# Smoothie_Stamp_Carrier_A3.net
KiCad netlist of a schematic drawn in EAGLE
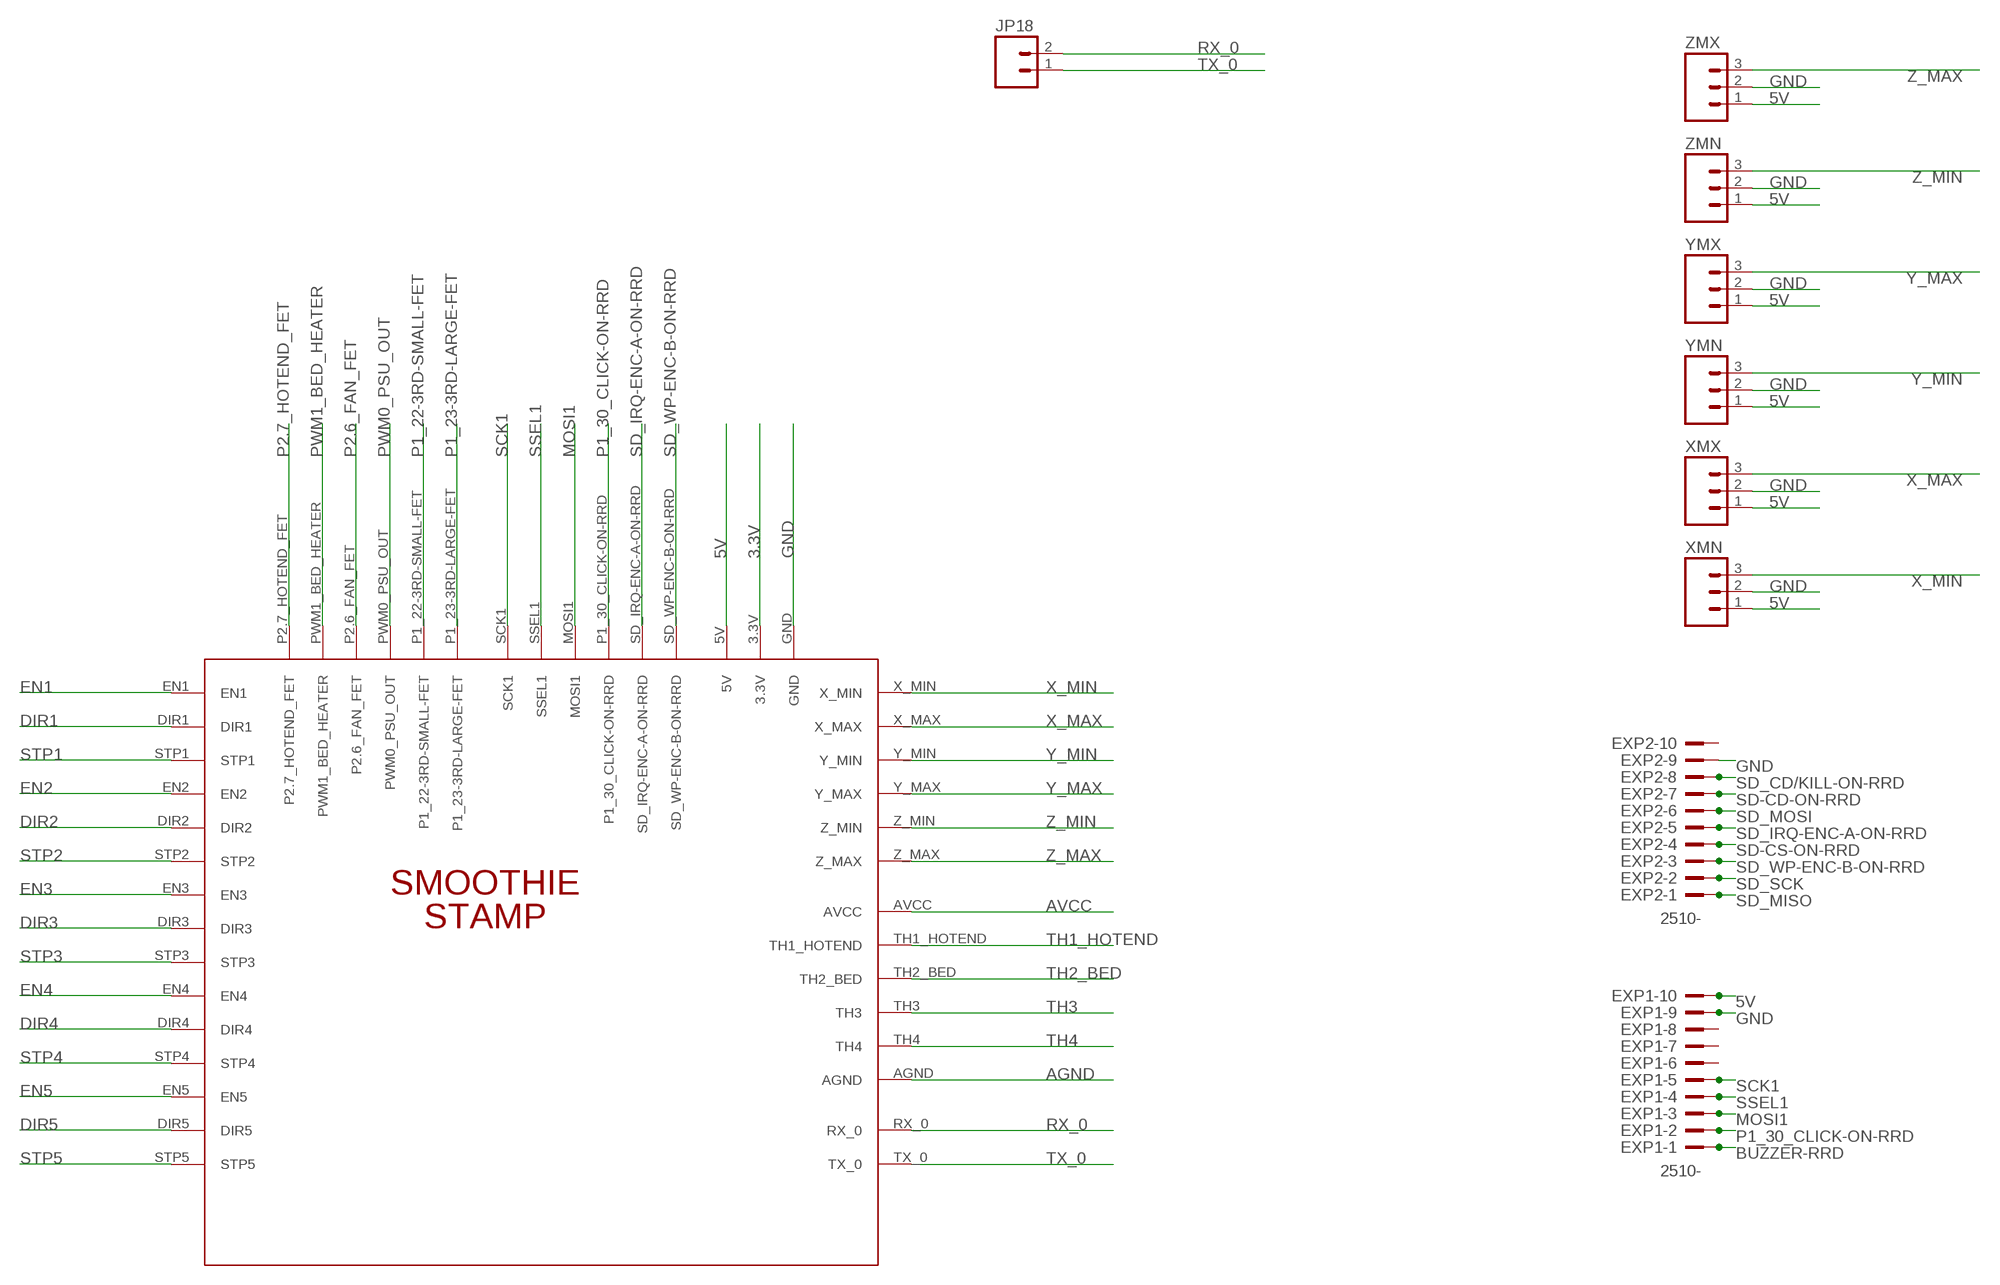
[diagram p0: schematic, sheet 1]
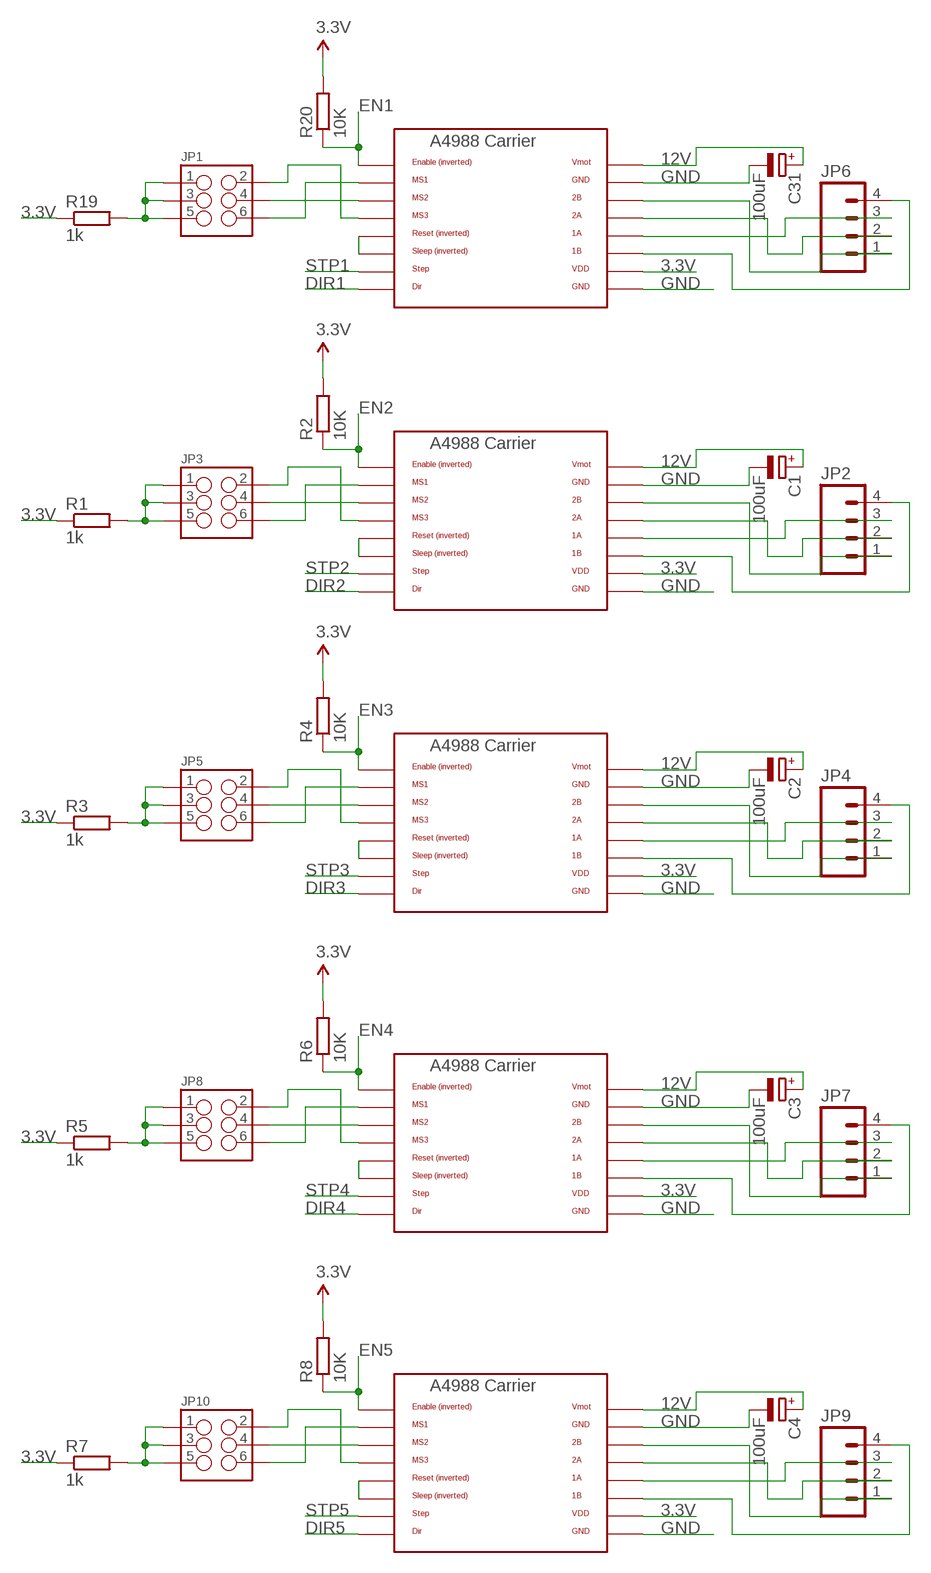
[diagram p1: schematic, sheet 2]
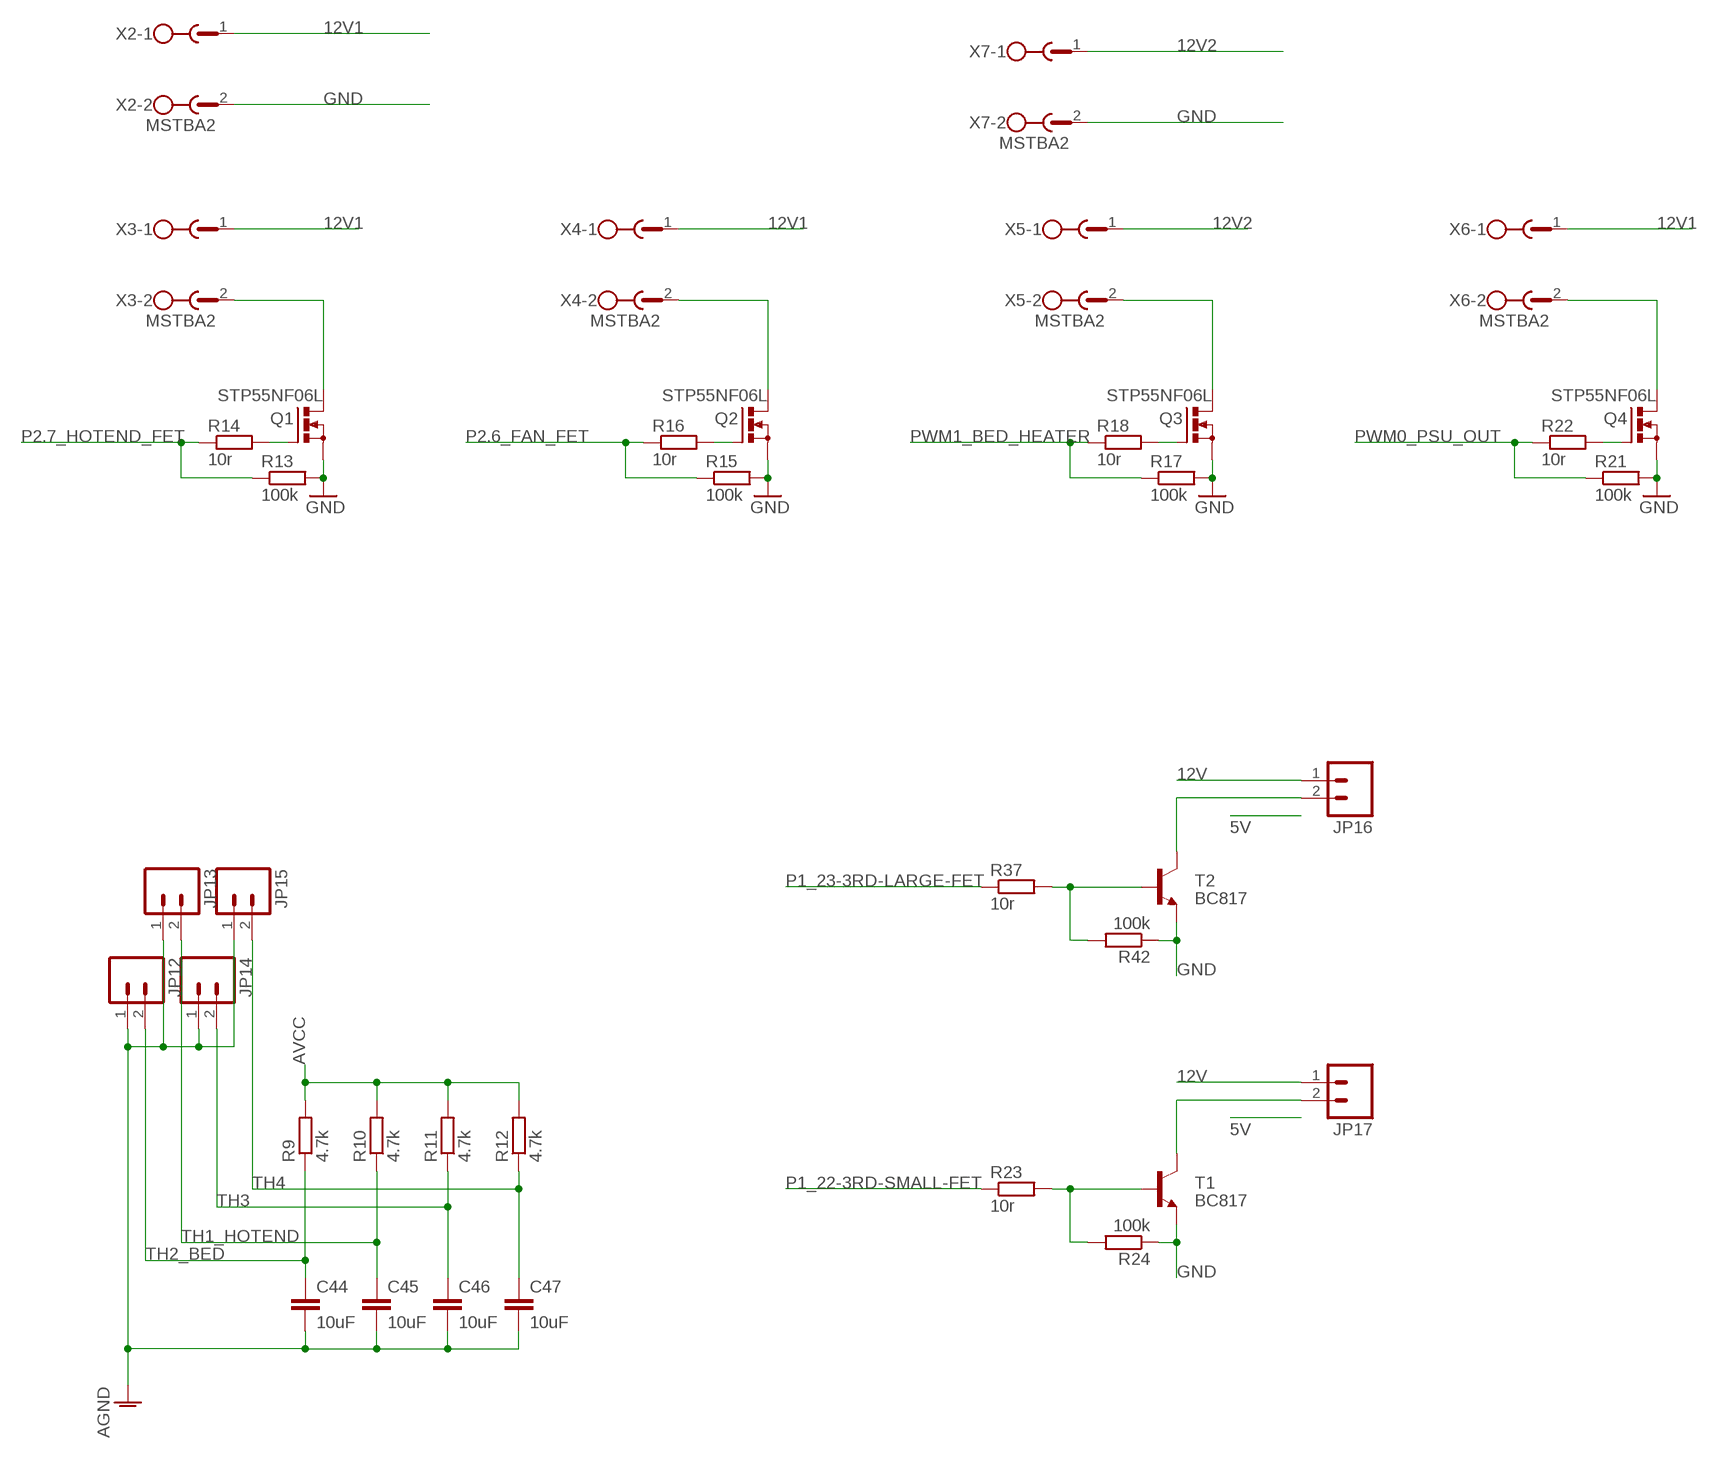
[diagram p2: schematic, sheet 3]
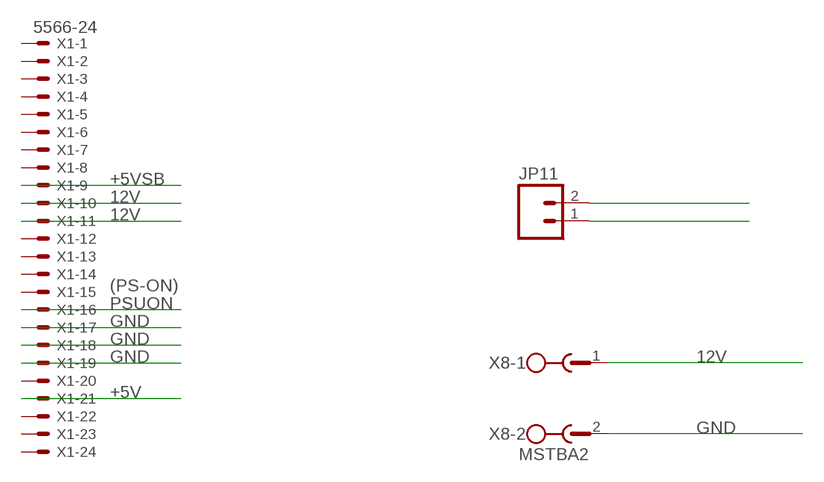
[diagram p3: schematic, sheet 4]

(export (version "E")
  (design (tool "Eeschema 10.0.6"))
  (components
    (comp (ref "EXP1")
      (value "2510-")
      (footprint "eagle-import:PAK100_2500-10")
      (fields (field (name "MF") "3M") (field (name "MPN") "2510-6002UB"))
      (libsource (lib "eagle-import") (part "2510-"))
    )
    (comp (ref "EXP2")
      (value "2510-")
      (footprint "eagle-import:PAK100_2500-10")
      (fields (field (name "MF") "3M") (field (name "MPN") "2510-6002UB"))
      (libsource (lib "eagle-import") (part "2510-"))
    )
    (comp (ref "JP18")
      (value "M02LOCK")
      (footprint "eagle-import:1X02_LOCK")
      (libsource (lib "eagle-import") (part "M02LOCK"))
    )
    (comp (ref "U$1")
      (value "SMOOTHIE-STAMPSMOOTHIE-STAMP-PTH")
      (footprint "eagle-import:SMOOTHIE-STAMP-PTH")
      (libsource (lib "eagle-import") (part "SMOOTHIE-STAMPSMOOTHIE-STAMP-PTH"))
    )
    (comp (ref "XMN")
      (value "M03LOCK")
      (footprint "eagle-import:1X03_LOCK")
      (libsource (lib "eagle-import") (part "M03LOCK"))
    )
    (comp (ref "XMX")
      (value "M03LOCK")
      (footprint "eagle-import:1X03_LOCK")
      (libsource (lib "eagle-import") (part "M03LOCK"))
    )
    (comp (ref "YMN")
      (value "M03LOCK")
      (footprint "eagle-import:1X03_LOCK")
      (libsource (lib "eagle-import") (part "M03LOCK"))
    )
    (comp (ref "YMX")
      (value "M03LOCK")
      (footprint "eagle-import:1X03_LOCK")
      (libsource (lib "eagle-import") (part "M03LOCK"))
    )
    (comp (ref "ZMN")
      (value "M03LOCK")
      (footprint "eagle-import:1X03_LOCK")
      (libsource (lib "eagle-import") (part "M03LOCK"))
    )
    (comp (ref "ZMX")
      (value "M03LOCK")
      (footprint "eagle-import:1X03_LOCK")
      (libsource (lib "eagle-import") (part "M03LOCK"))
    )
    (comp (ref "JP11")
      (value "M02LOCK")
      (footprint "eagle-import:1X02_LOCK")
      (libsource (lib "eagle-import") (part "M02LOCK"))
    )
    (comp (ref "X1")
      (value "5566-24")
      (footprint "eagle-import:5566-24")
      (libsource (lib "eagle-import") (part "5566-24"))
    )
    (comp (ref "X8")
      (value "MSTBA2")
      (footprint "eagle-import:MSTBA2")
      (fields (field (name "MF") "FARNELL") (field (name "MPN") "1757242"))
      (libsource (lib "eagle-import") (part "MSTBA2"))
    )
    (comp (ref "C1")
      (value "100uF")
      (footprint "eagle-import:E3,5-8")
      (libsource (lib "eagle-import") (part "CPOL-EUE3.5-8"))
    )
    (comp (ref "C2")
      (value "100uF")
      (footprint "eagle-import:E3,5-8")
      (libsource (lib "eagle-import") (part "CPOL-EUE3.5-8"))
    )
    (comp (ref "C3")
      (value "100uF")
      (footprint "eagle-import:E3,5-8")
      (libsource (lib "eagle-import") (part "CPOL-EUE3.5-8"))
    )
    (comp (ref "C4")
      (value "100uF")
      (footprint "eagle-import:E3,5-8")
      (libsource (lib "eagle-import") (part "CPOL-EUE3.5-8"))
    )
    (comp (ref "C31")
      (value "100uF")
      (footprint "eagle-import:E3,5-8")
      (libsource (lib "eagle-import") (part "CPOL-EUE3.5-8"))
    )
    (comp (ref "JP1")
      (value "M03X22X3_SILK_MALE_PTH")
      (footprint "eagle-import:2X3")
      (libsource (lib "eagle-import") (part "M03X22X3_SILK_MALE_PTH"))
    )
    (comp (ref "JP2")
      (value "M04POLAR_LOCK")
      (footprint "eagle-import:MOLEX-1X4_LOCK")
      (libsource (lib "eagle-import") (part "M04POLAR_LOCK"))
    )
    (comp (ref "JP3")
      (value "M03X22X3_SILK_MALE_PTH")
      (footprint "eagle-import:2X3")
      (libsource (lib "eagle-import") (part "M03X22X3_SILK_MALE_PTH"))
    )
    (comp (ref "JP4")
      (value "M04POLAR_LOCK")
      (footprint "eagle-import:MOLEX-1X4_LOCK")
      (libsource (lib "eagle-import") (part "M04POLAR_LOCK"))
    )
    (comp (ref "JP5")
      (value "M03X22X3_SILK_MALE_PTH")
      (footprint "eagle-import:2X3")
      (libsource (lib "eagle-import") (part "M03X22X3_SILK_MALE_PTH"))
    )
    (comp (ref "JP6")
      (value "M04POLAR_LOCK")
      (footprint "eagle-import:MOLEX-1X4_LOCK")
      (libsource (lib "eagle-import") (part "M04POLAR_LOCK"))
    )
    (comp (ref "JP7")
      (value "M04POLAR_LOCK")
      (footprint "eagle-import:MOLEX-1X4_LOCK")
      (libsource (lib "eagle-import") (part "M04POLAR_LOCK"))
    )
    (comp (ref "JP8")
      (value "M03X22X3_SILK_MALE_PTH")
      (footprint "eagle-import:2X3")
      (libsource (lib "eagle-import") (part "M03X22X3_SILK_MALE_PTH"))
    )
    (comp (ref "JP9")
      (value "M04POLAR_LOCK")
      (footprint "eagle-import:MOLEX-1X4_LOCK")
      (libsource (lib "eagle-import") (part "M04POLAR_LOCK"))
    )
    (comp (ref "JP10")
      (value "M03X22X3_SILK_MALE_PTH")
      (footprint "eagle-import:2X3")
      (libsource (lib "eagle-import") (part "M03X22X3_SILK_MALE_PTH"))
    )
    (comp (ref "R1")
      (value "1k")
      (footprint "eagle-import:0204V")
      (libsource (lib "eagle-import") (part "R-EU_0204/2V"))
    )
    (comp (ref "R2")
      (value "10K")
      (footprint "eagle-import:0204V")
      (libsource (lib "eagle-import") (part "R-EU_0204/2V"))
    )
    (comp (ref "R3")
      (value "1k")
      (footprint "eagle-import:0204V")
      (libsource (lib "eagle-import") (part "R-EU_0204/2V"))
    )
    (comp (ref "R4")
      (value "10K")
      (footprint "eagle-import:0204V")
      (libsource (lib "eagle-import") (part "R-EU_0204/2V"))
    )
    (comp (ref "R5")
      (value "1k")
      (footprint "eagle-import:0204V")
      (libsource (lib "eagle-import") (part "R-EU_0204/2V"))
    )
    (comp (ref "R6")
      (value "10K")
      (footprint "eagle-import:0204V")
      (libsource (lib "eagle-import") (part "R-EU_0204/2V"))
    )
    (comp (ref "R7")
      (value "1k")
      (footprint "eagle-import:0204V")
      (libsource (lib "eagle-import") (part "R-EU_0204/2V"))
    )
    (comp (ref "R8")
      (value "10K")
      (footprint "eagle-import:0204V")
      (libsource (lib "eagle-import") (part "R-EU_0204/2V"))
    )
    (comp (ref "R19")
      (value "1k")
      (footprint "eagle-import:0204V")
      (libsource (lib "eagle-import") (part "R-EU_0204/2V"))
    )
    (comp (ref "R20")
      (value "10K")
      (footprint "eagle-import:0204V")
      (libsource (lib "eagle-import") (part "R-EU_0204/2V"))
    )
    (comp (ref "U$2")
      (value "POLOLU_A4983CARRIER")
      (footprint "eagle-import:A4988BREAKOUT")
      (libsource (lib "eagle-import") (part "POLOLU_A4983CARRIER"))
    )
    (comp (ref "U$3")
      (value "POLOLU_A4983CARRIER")
      (footprint "eagle-import:A4988BREAKOUT")
      (libsource (lib "eagle-import") (part "POLOLU_A4983CARRIER"))
    )
    (comp (ref "U$4")
      (value "POLOLU_A4983CARRIER")
      (footprint "eagle-import:A4988BREAKOUT")
      (libsource (lib "eagle-import") (part "POLOLU_A4983CARRIER"))
    )
    (comp (ref "U$5")
      (value "POLOLU_A4983CARRIER")
      (footprint "eagle-import:A4988BREAKOUT")
      (libsource (lib "eagle-import") (part "POLOLU_A4983CARRIER"))
    )
    (comp (ref "U$6")
      (value "POLOLU_A4983CARRIER")
      (footprint "eagle-import:A4988BREAKOUT")
      (libsource (lib "eagle-import") (part "POLOLU_A4983CARRIER"))
    )
    (comp (ref "C44")
      (value "10uF")
      (footprint "eagle-import:C050-025X075")
      (libsource (lib "eagle-import") (part "C-EU050-025X075"))
    )
    (comp (ref "C45")
      (value "10uF")
      (footprint "eagle-import:C050-025X075")
      (libsource (lib "eagle-import") (part "C-EU050-025X075"))
    )
    (comp (ref "C46")
      (value "10uF")
      (footprint "eagle-import:C050-025X075")
      (libsource (lib "eagle-import") (part "C-EU050-025X075"))
    )
    (comp (ref "C47")
      (value "10uF")
      (footprint "eagle-import:C050-025X075")
      (libsource (lib "eagle-import") (part "C-EU050-025X075"))
    )
    (comp (ref "JP12")
      (value "M02PTH")
      (footprint "eagle-import:1X02")
      (libsource (lib "eagle-import") (part "M02PTH"))
    )
    (comp (ref "JP13")
      (value "M02PTH")
      (footprint "eagle-import:1X02")
      (libsource (lib "eagle-import") (part "M02PTH"))
    )
    (comp (ref "JP14")
      (value "M02PTH")
      (footprint "eagle-import:1X02")
      (libsource (lib "eagle-import") (part "M02PTH"))
    )
    (comp (ref "JP15")
      (value "M02PTH")
      (footprint "eagle-import:1X02")
      (libsource (lib "eagle-import") (part "M02PTH"))
    )
    (comp (ref "JP16")
      (value "M02LOCK")
      (footprint "eagle-import:1X02_LOCK")
      (libsource (lib "eagle-import") (part "M02LOCK"))
    )
    (comp (ref "JP17")
      (value "M02LOCK")
      (footprint "eagle-import:1X02_LOCK")
      (libsource (lib "eagle-import") (part "M02LOCK"))
    )
    (comp (ref "Q1")
      (value "STP55NF06L")
      (footprint "eagle-import:TO220BV")
      (libsource (lib "eagle-import") (part "IRF512"))
    )
    (comp (ref "Q2")
      (value "STP55NF06L")
      (footprint "eagle-import:TO220BV")
      (libsource (lib "eagle-import") (part "IRF512"))
    )
    (comp (ref "Q3")
      (value "STP55NF06L")
      (footprint "eagle-import:TO220BV")
      (libsource (lib "eagle-import") (part "IRF512"))
    )
    (comp (ref "Q4")
      (value "STP55NF06L")
      (footprint "eagle-import:TO220BV")
      (libsource (lib "eagle-import") (part "IRF512"))
    )
    (comp (ref "R9")
      (value "4.7k")
      (footprint "eagle-import:0207_5V")
      (libsource (lib "eagle-import") (part "R-EU_0207/5V"))
    )
    (comp (ref "R10")
      (value "4.7k")
      (footprint "eagle-import:0207_5V")
      (libsource (lib "eagle-import") (part "R-EU_0207/5V"))
    )
    (comp (ref "R11")
      (value "4.7k")
      (footprint "eagle-import:0207_5V")
      (libsource (lib "eagle-import") (part "R-EU_0207/5V"))
    )
    (comp (ref "R12")
      (value "4.7k")
      (footprint "eagle-import:0207_5V")
      (libsource (lib "eagle-import") (part "R-EU_0207/5V"))
    )
    (comp (ref "R13")
      (value "100k")
      (footprint "eagle-import:0204V")
      (libsource (lib "eagle-import") (part "R-EU_0204/2V"))
    )
    (comp (ref "R14")
      (value "10r")
      (footprint "eagle-import:0204V")
      (libsource (lib "eagle-import") (part "R-EU_0204/2V"))
    )
    (comp (ref "R15")
      (value "100k")
      (footprint "eagle-import:0204V")
      (libsource (lib "eagle-import") (part "R-EU_0204/2V"))
    )
    (comp (ref "R16")
      (value "10r")
      (footprint "eagle-import:0204V")
      (libsource (lib "eagle-import") (part "R-EU_0204/2V"))
    )
    (comp (ref "R17")
      (value "100k")
      (footprint "eagle-import:0204V")
      (libsource (lib "eagle-import") (part "R-EU_0204/2V"))
    )
    (comp (ref "R18")
      (value "10r")
      (footprint "eagle-import:0204V")
      (libsource (lib "eagle-import") (part "R-EU_0204/2V"))
    )
    (comp (ref "R21")
      (value "100k")
      (footprint "eagle-import:0204V")
      (libsource (lib "eagle-import") (part "R-EU_0204/2V"))
    )
    (comp (ref "R22")
      (value "10r")
      (footprint "eagle-import:0204V")
      (libsource (lib "eagle-import") (part "R-EU_0204/2V"))
    )
    (comp (ref "R23")
      (value "10r")
      (footprint "eagle-import:0204V")
      (libsource (lib "eagle-import") (part "R-EU_0204/2V"))
    )
    (comp (ref "R24")
      (value "100k")
      (footprint "eagle-import:0204V")
      (libsource (lib "eagle-import") (part "R-EU_0204/2V"))
    )
    (comp (ref "R37")
      (value "10r")
      (footprint "eagle-import:0204V")
      (libsource (lib "eagle-import") (part "R-EU_0204/2V"))
    )
    (comp (ref "R42")
      (value "100k")
      (footprint "eagle-import:0204V")
      (libsource (lib "eagle-import") (part "R-EU_0204/2V"))
    )
    (comp (ref "T1")
      (value "BC817")
      (footprint "eagle-import:TO-92")
      (libsource (lib "eagle-import") (part "TRANSISTOR_NPN2N3904"))
    )
    (comp (ref "T2")
      (value "BC817")
      (footprint "eagle-import:TO-92")
      (libsource (lib "eagle-import") (part "TRANSISTOR_NPN2N3904"))
    )
    (comp (ref "X2")
      (value "MSTBA2")
      (footprint "eagle-import:MSTBA2")
      (fields (field (name "MF") "FARNELL") (field (name "MPN") "1757242"))
      (libsource (lib "eagle-import") (part "MSTBA2"))
    )
    (comp (ref "X3")
      (value "MSTBA2")
      (footprint "eagle-import:MSTBA2")
      (fields (field (name "MF") "FARNELL") (field (name "MPN") "1757242"))
      (libsource (lib "eagle-import") (part "MSTBA2"))
    )
    (comp (ref "X4")
      (value "MSTBA2")
      (footprint "eagle-import:MSTBA2")
      (fields (field (name "MF") "FARNELL") (field (name "MPN") "1757242"))
      (libsource (lib "eagle-import") (part "MSTBA2"))
    )
    (comp (ref "X5")
      (value "MSTBA2")
      (footprint "eagle-import:MSTBA2")
      (fields (field (name "MF") "FARNELL") (field (name "MPN") "1757242"))
      (libsource (lib "eagle-import") (part "MSTBA2"))
    )
    (comp (ref "X6")
      (value "MSTBA2")
      (footprint "eagle-import:MSTBA2")
      (fields (field (name "MF") "FARNELL") (field (name "MPN") "1757242"))
      (libsource (lib "eagle-import") (part "MSTBA2"))
    )
    (comp (ref "X7")
      (value "MSTBA2")
      (footprint "eagle-import:MSTBA2")
      (fields (field (name "MF") "FARNELL") (field (name "MPN") "1757242"))
      (libsource (lib "eagle-import") (part "MSTBA2"))
    )
  )
  (nets
    (net (code "1") (name "+5V") (class "Default")
      (node (ref "X1") (pin "21") (pinfunction "S_21") (pintype "passive"))
    )
    (net (code "2") (name "+5VSB") (class "Default")
      (node (ref "X1") (pin "9") (pinfunction "S_9") (pintype "passive"))
    )
    (net (code "3") (name "3.3V") (class "Default")
      (node (ref "R1") (pin "1") (pinfunction "1_1") (pintype "passive"))
      (node (ref "R19") (pin "1") (pinfunction "1_1") (pintype "passive"))
      (node (ref "R2") (pin "2") (pinfunction "2_2") (pintype "passive"))
      (node (ref "R20") (pin "2") (pinfunction "2_2") (pintype "passive"))
      (node (ref "R3") (pin "1") (pinfunction "1_1") (pintype "passive"))
      (node (ref "R4") (pin "2") (pinfunction "2_2") (pintype "passive"))
      (node (ref "R5") (pin "1") (pinfunction "1_1") (pintype "passive"))
      (node (ref "R6") (pin "2") (pinfunction "2_2") (pintype "passive"))
      (node (ref "R7") (pin "1") (pinfunction "1_1") (pintype "passive"))
      (node (ref "R8") (pin "2") (pinfunction "2_2") (pintype "passive"))
      (node (ref "U$1") (pin "3.3V") (pinfunction "3.3V_3.3V") (pintype "bidirectional"))
      (node (ref "U$2") (pin "VDD") (pinfunction "VDD_VDD") (pintype "power_in"))
      (node (ref "U$3") (pin "VDD") (pinfunction "VDD_VDD") (pintype "power_in"))
      (node (ref "U$4") (pin "VDD") (pinfunction "VDD_VDD") (pintype "power_in"))
      (node (ref "U$5") (pin "VDD") (pinfunction "VDD_VDD") (pintype "power_in"))
      (node (ref "U$6") (pin "VDD") (pinfunction "VDD_VDD") (pintype "power_in"))
    )
    (net (code "4") (name "5V") (class "Default")
      (node (ref "EXP1") (pin "10") (pinfunction "KL_10") (pintype "passive"))
      (node (ref "U$1") (pin "5V") (pinfunction "5V_5V") (pintype "bidirectional"))
      (node (ref "XMN") (pin "1") (pinfunction "1_1") (pintype "passive"))
      (node (ref "XMX") (pin "1") (pinfunction "1_1") (pintype "passive"))
      (node (ref "YMN") (pin "1") (pinfunction "1_1") (pintype "passive"))
      (node (ref "YMX") (pin "1") (pinfunction "1_1") (pintype "passive"))
      (node (ref "ZMN") (pin "1") (pinfunction "1_1") (pintype "passive"))
      (node (ref "ZMX") (pin "1") (pinfunction "1_1") (pintype "passive"))
    )
    (net (code "5") (name "12V") (class "Default")
      (node (ref "C1") (pin "+") (pinfunction "+_+") (pintype "passive"))
      (node (ref "C2") (pin "+") (pinfunction "+_+") (pintype "passive"))
      (node (ref "C3") (pin "+") (pinfunction "+_+") (pintype "passive"))
      (node (ref "C31") (pin "+") (pinfunction "+_+") (pintype "passive"))
      (node (ref "C4") (pin "+") (pinfunction "+_+") (pintype "passive"))
      (node (ref "JP16") (pin "1") (pinfunction "1_1") (pintype "passive"))
      (node (ref "JP17") (pin "1") (pinfunction "1_1") (pintype "passive"))
      (node (ref "U$2") (pin "VMOT") (pinfunction "VMOT_VMOT") (pintype "power_in"))
      (node (ref "U$3") (pin "VMOT") (pinfunction "VMOT_VMOT") (pintype "power_in"))
      (node (ref "U$4") (pin "VMOT") (pinfunction "VMOT_VMOT") (pintype "power_in"))
      (node (ref "U$5") (pin "VMOT") (pinfunction "VMOT_VMOT") (pintype "power_in"))
      (node (ref "U$6") (pin "VMOT") (pinfunction "VMOT_VMOT") (pintype "power_in"))
      (node (ref "X1") (pin "10") (pinfunction "S_10") (pintype "passive"))
      (node (ref "X1") (pin "11") (pinfunction "S_11") (pintype "passive"))
      (node (ref "X8") (pin "1") (pinfunction "1_1") (pintype "passive"))
    )
    (net (code "6") (name "12V1") (class "Default")
      (node (ref "X2") (pin "1") (pinfunction "1_1") (pintype "passive"))
      (node (ref "X3") (pin "1") (pinfunction "1_1") (pintype "passive"))
      (node (ref "X4") (pin "1") (pinfunction "1_1") (pintype "passive"))
      (node (ref "X6") (pin "1") (pinfunction "1_1") (pintype "passive"))
    )
    (net (code "7") (name "12V2") (class "Default")
      (node (ref "X5") (pin "1") (pinfunction "1_1") (pintype "passive"))
      (node (ref "X7") (pin "1") (pinfunction "1_1") (pintype "passive"))
    )
    (net (code "8") (name "AGND") (class "Default")
      (node (ref "C44") (pin "2") (pinfunction "2_2") (pintype "passive"))
      (node (ref "C45") (pin "2") (pinfunction "2_2") (pintype "passive"))
      (node (ref "C46") (pin "2") (pinfunction "2_2") (pintype "passive"))
      (node (ref "C47") (pin "2") (pinfunction "2_2") (pintype "passive"))
      (node (ref "JP12") (pin "1") (pinfunction "1_1") (pintype "passive"))
      (node (ref "JP13") (pin "1") (pinfunction "1_1") (pintype "passive"))
      (node (ref "JP14") (pin "1") (pinfunction "1_1") (pintype "passive"))
      (node (ref "JP15") (pin "1") (pinfunction "1_1") (pintype "passive"))
      (node (ref "U$1") (pin "AGND") (pinfunction "AGND_AGND") (pintype "bidirectional"))
    )
    (net (code "9") (name "AVCC") (class "Default")
      (node (ref "R10") (pin "2") (pinfunction "2_2") (pintype "passive"))
      (node (ref "R11") (pin "2") (pinfunction "2_2") (pintype "passive"))
      (node (ref "R12") (pin "2") (pinfunction "2_2") (pintype "passive"))
      (node (ref "R9") (pin "2") (pinfunction "2_2") (pintype "passive"))
      (node (ref "U$1") (pin "AVCC") (pinfunction "AVCC_AVCC") (pintype "bidirectional"))
    )
    (net (code "10") (name "BUZZER-RRD") (class "Default")
      (node (ref "EXP1") (pin "1") (pinfunction "KL_1") (pintype "passive"))
    )
    (net (code "11") (name "DIR1") (class "Default")
      (node (ref "U$1") (pin "DIR1") (pinfunction "DIR1_DIR1") (pintype "bidirectional"))
      (node (ref "U$2") (pin "DIR") (pinfunction "DIR_DIR") (pintype "input"))
    )
    (net (code "12") (name "DIR2") (class "Default")
      (node (ref "U$1") (pin "DIR2") (pinfunction "DIR2_DIR2") (pintype "bidirectional"))
      (node (ref "U$3") (pin "DIR") (pinfunction "DIR_DIR") (pintype "input"))
    )
    (net (code "13") (name "DIR3") (class "Default")
      (node (ref "U$1") (pin "DIR3") (pinfunction "DIR3_DIR3") (pintype "bidirectional"))
      (node (ref "U$4") (pin "DIR") (pinfunction "DIR_DIR") (pintype "input"))
    )
    (net (code "14") (name "DIR4") (class "Default")
      (node (ref "U$1") (pin "DIR4") (pinfunction "DIR4_DIR4") (pintype "bidirectional"))
      (node (ref "U$5") (pin "DIR") (pinfunction "DIR_DIR") (pintype "input"))
    )
    (net (code "15") (name "DIR5") (class "Default")
      (node (ref "U$1") (pin "DIR5") (pinfunction "DIR5_DIR5") (pintype "bidirectional"))
      (node (ref "U$6") (pin "DIR") (pinfunction "DIR_DIR") (pintype "input"))
    )
    (net (code "16") (name "EN1") (class "Default")
      (node (ref "R20") (pin "1") (pinfunction "1_1") (pintype "passive"))
      (node (ref "U$1") (pin "EN1") (pinfunction "EN1_EN1") (pintype "bidirectional"))
      (node (ref "U$2") (pin "EN") (pinfunction "EN_EN") (pintype "input"))
    )
    (net (code "17") (name "EN2") (class "Default")
      (node (ref "R2") (pin "1") (pinfunction "1_1") (pintype "passive"))
      (node (ref "U$1") (pin "EN2") (pinfunction "EN2_EN2") (pintype "bidirectional"))
      (node (ref "U$3") (pin "EN") (pinfunction "EN_EN") (pintype "input"))
    )
    (net (code "18") (name "EN3") (class "Default")
      (node (ref "R4") (pin "1") (pinfunction "1_1") (pintype "passive"))
      (node (ref "U$1") (pin "EN3") (pinfunction "EN3_EN3") (pintype "bidirectional"))
      (node (ref "U$4") (pin "EN") (pinfunction "EN_EN") (pintype "input"))
    )
    (net (code "19") (name "EN4") (class "Default")
      (node (ref "R6") (pin "1") (pinfunction "1_1") (pintype "passive"))
      (node (ref "U$1") (pin "EN4") (pinfunction "EN4_EN4") (pintype "bidirectional"))
      (node (ref "U$5") (pin "EN") (pinfunction "EN_EN") (pintype "input"))
    )
    (net (code "20") (name "EN5") (class "Default")
      (node (ref "R8") (pin "1") (pinfunction "1_1") (pintype "passive"))
      (node (ref "U$1") (pin "EN5") (pinfunction "EN5_EN5") (pintype "bidirectional"))
      (node (ref "U$6") (pin "EN") (pinfunction "EN_EN") (pintype "input"))
    )
    (net (code "21") (name "GND") (class "Default")
      (node (ref "C1") (pin "-") (pinfunction "-_-") (pintype "passive"))
      (node (ref "C2") (pin "-") (pinfunction "-_-") (pintype "passive"))
      (node (ref "C3") (pin "-") (pinfunction "-_-") (pintype "passive"))
      (node (ref "C31") (pin "-") (pinfunction "-_-") (pintype "passive"))
      (node (ref "C4") (pin "-") (pinfunction "-_-") (pintype "passive"))
      (node (ref "EXP1") (pin "9") (pinfunction "KL_9") (pintype "passive"))
      (node (ref "EXP2") (pin "9") (pinfunction "KL_9") (pintype "passive"))
      (node (ref "JP11") (pin "1") (pinfunction "1_1") (pintype "passive"))
      (node (ref "Q1") (pin "S") (pinfunction "S_S") (pintype "passive"))
      (node (ref "Q2") (pin "S") (pinfunction "S_S") (pintype "passive"))
      (node (ref "Q3") (pin "S") (pinfunction "S_S") (pintype "passive"))
      (node (ref "Q4") (pin "S") (pinfunction "S_S") (pintype "passive"))
      (node (ref "R13") (pin "2") (pinfunction "2_2") (pintype "passive"))
      (node (ref "R15") (pin "2") (pinfunction "2_2") (pintype "passive"))
      (node (ref "R17") (pin "2") (pinfunction "2_2") (pintype "passive"))
      (node (ref "R21") (pin "2") (pinfunction "2_2") (pintype "passive"))
      (node (ref "R24") (pin "1") (pinfunction "1_1") (pintype "passive"))
      (node (ref "R42") (pin "1") (pinfunction "1_1") (pintype "passive"))
      (node (ref "T1") (pin "1") (pinfunction "E_1") (pintype "passive"))
      (node (ref "T2") (pin "1") (pinfunction "E_1") (pintype "passive"))
      (node (ref "U$1") (pin "GND") (pinfunction "GND_GND") (pintype "bidirectional"))
      (node (ref "U$2") (pin "GND") (pinfunction "GND_GND") (pintype "power_in"))
      (node (ref "U$2") (pin "GND@0") (pinfunction "GND_GND@0") (pintype "power_in"))
      (node (ref "U$3") (pin "GND") (pinfunction "GND_GND") (pintype "power_in"))
      (node (ref "U$3") (pin "GND@0") (pinfunction "GND_GND@0") (pintype "power_in"))
      (node (ref "U$4") (pin "GND") (pinfunction "GND_GND") (pintype "power_in"))
      (node (ref "U$4") (pin "GND@0") (pinfunction "GND_GND@0") (pintype "power_in"))
      (node (ref "U$5") (pin "GND") (pinfunction "GND_GND") (pintype "power_in"))
      (node (ref "U$5") (pin "GND@0") (pinfunction "GND_GND@0") (pintype "power_in"))
      (node (ref "U$6") (pin "GND") (pinfunction "GND_GND") (pintype "power_in"))
      (node (ref "U$6") (pin "GND@0") (pinfunction "GND_GND@0") (pintype "power_in"))
      (node (ref "X1") (pin "17") (pinfunction "S_17") (pintype "passive"))
      (node (ref "X1") (pin "18") (pinfunction "S_18") (pintype "passive"))
      (node (ref "X1") (pin "19") (pinfunction "S_19") (pintype "passive"))
      (node (ref "X2") (pin "2") (pinfunction "1_2") (pintype "passive"))
      (node (ref "X7") (pin "2") (pinfunction "1_2") (pintype "passive"))
      (node (ref "X8") (pin "2") (pinfunction "1_2") (pintype "passive"))
      (node (ref "XMN") (pin "2") (pinfunction "2_2") (pintype "passive"))
      (node (ref "XMX") (pin "2") (pinfunction "2_2") (pintype "passive"))
      (node (ref "YMN") (pin "2") (pinfunction "2_2") (pintype "passive"))
      (node (ref "YMX") (pin "2") (pinfunction "2_2") (pintype "passive"))
      (node (ref "ZMN") (pin "2") (pinfunction "2_2") (pintype "passive"))
      (node (ref "ZMX") (pin "2") (pinfunction "2_2") (pintype "passive"))
    )
    (net (code "22") (name "MOSI1") (class "Default")
      (node (ref "EXP1") (pin "3") (pinfunction "KL_3") (pintype "passive"))
      (node (ref "U$1") (pin "MOSI1") (pinfunction "MOSI1_MOSI1") (pintype "bidirectional"))
    )
    (net (code "23") (name "Net-(JP1-Pad1)") (class "Default")
      (node (ref "JP1") (pin "1") (pinfunction "1_1") (pintype "bidirectional"))
      (node (ref "JP1") (pin "3") (pinfunction "3_3") (pintype "bidirectional"))
      (node (ref "JP1") (pin "5") (pinfunction "5_5") (pintype "bidirectional"))
      (node (ref "R19") (pin "2") (pinfunction "2_2") (pintype "passive"))
    )
    (net (code "24") (name "Net-(JP1-Pad2)") (class "Default")
      (node (ref "JP1") (pin "2") (pinfunction "2_2") (pintype "bidirectional"))
      (node (ref "U$2") (pin "MS3") (pinfunction "MS3_MS3") (pintype "input"))
    )
    (net (code "25") (name "Net-(JP1-Pad4)") (class "Default")
      (node (ref "JP1") (pin "4") (pinfunction "4_4") (pintype "bidirectional"))
      (node (ref "U$2") (pin "MS2") (pinfunction "MS2_MS2") (pintype "input"))
    )
    (net (code "26") (name "Net-(JP1-Pad6)") (class "Default")
      (node (ref "JP1") (pin "6") (pinfunction "6_6") (pintype "bidirectional"))
      (node (ref "U$2") (pin "MS1") (pinfunction "MS1_MS1") (pintype "input"))
    )
    (net (code "27") (name "Net-(JP2-Pad1)") (class "Default")
      (node (ref "JP2") (pin "1") (pinfunction "1_1") (pintype "passive"))
      (node (ref "U$3") (pin "2B") (pinfunction "2B_2B") (pintype "output"))
    )
    (net (code "28") (name "Net-(JP2-Pad2)") (class "Default")
      (node (ref "JP2") (pin "2") (pinfunction "2_2") (pintype "passive"))
      (node (ref "U$3") (pin "2A") (pinfunction "2A_2A") (pintype "output"))
    )
    (net (code "29") (name "Net-(JP2-Pad3)") (class "Default")
      (node (ref "JP2") (pin "3") (pinfunction "3_3") (pintype "passive"))
      (node (ref "U$3") (pin "1A") (pinfunction "1A_1A") (pintype "output"))
    )
    (net (code "30") (name "Net-(JP2-Pad4)") (class "Default")
      (node (ref "JP2") (pin "4") (pinfunction "4_4") (pintype "passive"))
      (node (ref "U$3") (pin "1B") (pinfunction "1B_1B") (pintype "output"))
    )
    (net (code "31") (name "Net-(JP3-Pad1)") (class "Default")
      (node (ref "JP3") (pin "1") (pinfunction "1_1") (pintype "bidirectional"))
      (node (ref "JP3") (pin "3") (pinfunction "3_3") (pintype "bidirectional"))
      (node (ref "JP3") (pin "5") (pinfunction "5_5") (pintype "bidirectional"))
      (node (ref "R1") (pin "2") (pinfunction "2_2") (pintype "passive"))
    )
    (net (code "32") (name "Net-(JP3-Pad2)") (class "Default")
      (node (ref "JP3") (pin "2") (pinfunction "2_2") (pintype "bidirectional"))
      (node (ref "U$3") (pin "MS3") (pinfunction "MS3_MS3") (pintype "input"))
    )
    (net (code "33") (name "Net-(JP3-Pad4)") (class "Default")
      (node (ref "JP3") (pin "4") (pinfunction "4_4") (pintype "bidirectional"))
      (node (ref "U$3") (pin "MS2") (pinfunction "MS2_MS2") (pintype "input"))
    )
    (net (code "34") (name "Net-(JP3-Pad6)") (class "Default")
      (node (ref "JP3") (pin "6") (pinfunction "6_6") (pintype "bidirectional"))
      (node (ref "U$3") (pin "MS1") (pinfunction "MS1_MS1") (pintype "input"))
    )
    (net (code "35") (name "Net-(JP4-Pad1)") (class "Default")
      (node (ref "JP4") (pin "1") (pinfunction "1_1") (pintype "passive"))
      (node (ref "U$4") (pin "2B") (pinfunction "2B_2B") (pintype "output"))
    )
    (net (code "36") (name "Net-(JP4-Pad2)") (class "Default")
      (node (ref "JP4") (pin "2") (pinfunction "2_2") (pintype "passive"))
      (node (ref "U$4") (pin "2A") (pinfunction "2A_2A") (pintype "output"))
    )
    (net (code "37") (name "Net-(JP4-Pad3)") (class "Default")
      (node (ref "JP4") (pin "3") (pinfunction "3_3") (pintype "passive"))
      (node (ref "U$4") (pin "1A") (pinfunction "1A_1A") (pintype "output"))
    )
    (net (code "38") (name "Net-(JP4-Pad4)") (class "Default")
      (node (ref "JP4") (pin "4") (pinfunction "4_4") (pintype "passive"))
      (node (ref "U$4") (pin "1B") (pinfunction "1B_1B") (pintype "output"))
    )
    (net (code "39") (name "Net-(JP5-Pad1)") (class "Default")
      (node (ref "JP5") (pin "1") (pinfunction "1_1") (pintype "bidirectional"))
      (node (ref "JP5") (pin "3") (pinfunction "3_3") (pintype "bidirectional"))
      (node (ref "JP5") (pin "5") (pinfunction "5_5") (pintype "bidirectional"))
      (node (ref "R3") (pin "2") (pinfunction "2_2") (pintype "passive"))
    )
    (net (code "40") (name "Net-(JP5-Pad2)") (class "Default")
      (node (ref "JP5") (pin "2") (pinfunction "2_2") (pintype "bidirectional"))
      (node (ref "U$4") (pin "MS3") (pinfunction "MS3_MS3") (pintype "input"))
    )
    (net (code "41") (name "Net-(JP5-Pad4)") (class "Default")
      (node (ref "JP5") (pin "4") (pinfunction "4_4") (pintype "bidirectional"))
      (node (ref "U$4") (pin "MS2") (pinfunction "MS2_MS2") (pintype "input"))
    )
    (net (code "42") (name "Net-(JP5-Pad6)") (class "Default")
      (node (ref "JP5") (pin "6") (pinfunction "6_6") (pintype "bidirectional"))
      (node (ref "U$4") (pin "MS1") (pinfunction "MS1_MS1") (pintype "input"))
    )
    (net (code "43") (name "Net-(JP6-Pad1)") (class "Default")
      (node (ref "JP6") (pin "1") (pinfunction "1_1") (pintype "passive"))
      (node (ref "U$2") (pin "2B") (pinfunction "2B_2B") (pintype "output"))
    )
    (net (code "44") (name "Net-(JP6-Pad2)") (class "Default")
      (node (ref "JP6") (pin "2") (pinfunction "2_2") (pintype "passive"))
      (node (ref "U$2") (pin "2A") (pinfunction "2A_2A") (pintype "output"))
    )
    (net (code "45") (name "Net-(JP6-Pad3)") (class "Default")
      (node (ref "JP6") (pin "3") (pinfunction "3_3") (pintype "passive"))
      (node (ref "U$2") (pin "1A") (pinfunction "1A_1A") (pintype "output"))
    )
    (net (code "46") (name "Net-(JP6-Pad4)") (class "Default")
      (node (ref "JP6") (pin "4") (pinfunction "4_4") (pintype "passive"))
      (node (ref "U$2") (pin "1B") (pinfunction "1B_1B") (pintype "output"))
    )
    (net (code "47") (name "Net-(JP7-Pad1)") (class "Default")
      (node (ref "JP7") (pin "1") (pinfunction "1_1") (pintype "passive"))
      (node (ref "U$5") (pin "2B") (pinfunction "2B_2B") (pintype "output"))
    )
    (net (code "48") (name "Net-(JP7-Pad2)") (class "Default")
      (node (ref "JP7") (pin "2") (pinfunction "2_2") (pintype "passive"))
      (node (ref "U$5") (pin "2A") (pinfunction "2A_2A") (pintype "output"))
    )
    (net (code "49") (name "Net-(JP7-Pad3)") (class "Default")
      (node (ref "JP7") (pin "3") (pinfunction "3_3") (pintype "passive"))
      (node (ref "U$5") (pin "1A") (pinfunction "1A_1A") (pintype "output"))
    )
    (net (code "50") (name "Net-(JP7-Pad4)") (class "Default")
      (node (ref "JP7") (pin "4") (pinfunction "4_4") (pintype "passive"))
      (node (ref "U$5") (pin "1B") (pinfunction "1B_1B") (pintype "output"))
    )
    (net (code "51") (name "Net-(JP8-Pad1)") (class "Default")
      (node (ref "JP8") (pin "1") (pinfunction "1_1") (pintype "bidirectional"))
      (node (ref "JP8") (pin "3") (pinfunction "3_3") (pintype "bidirectional"))
      (node (ref "JP8") (pin "5") (pinfunction "5_5") (pintype "bidirectional"))
      (node (ref "R5") (pin "2") (pinfunction "2_2") (pintype "passive"))
    )
    (net (code "52") (name "Net-(JP8-Pad2)") (class "Default")
      (node (ref "JP8") (pin "2") (pinfunction "2_2") (pintype "bidirectional"))
      (node (ref "U$5") (pin "MS3") (pinfunction "MS3_MS3") (pintype "input"))
    )
    (net (code "53") (name "Net-(JP8-Pad4)") (class "Default")
      (node (ref "JP8") (pin "4") (pinfunction "4_4") (pintype "bidirectional"))
      (node (ref "U$5") (pin "MS2") (pinfunction "MS2_MS2") (pintype "input"))
    )
    (net (code "54") (name "Net-(JP8-Pad6)") (class "Default")
      (node (ref "JP8") (pin "6") (pinfunction "6_6") (pintype "bidirectional"))
      (node (ref "U$5") (pin "MS1") (pinfunction "MS1_MS1") (pintype "input"))
    )
    (net (code "55") (name "Net-(JP9-Pad1)") (class "Default")
      (node (ref "JP9") (pin "1") (pinfunction "1_1") (pintype "passive"))
      (node (ref "U$6") (pin "2B") (pinfunction "2B_2B") (pintype "output"))
    )
    (net (code "56") (name "Net-(JP9-Pad2)") (class "Default")
      (node (ref "JP9") (pin "2") (pinfunction "2_2") (pintype "passive"))
      (node (ref "U$6") (pin "2A") (pinfunction "2A_2A") (pintype "output"))
    )
    (net (code "57") (name "Net-(JP9-Pad3)") (class "Default")
      (node (ref "JP9") (pin "3") (pinfunction "3_3") (pintype "passive"))
      (node (ref "U$6") (pin "1A") (pinfunction "1A_1A") (pintype "output"))
    )
    (net (code "58") (name "Net-(JP9-Pad4)") (class "Default")
      (node (ref "JP9") (pin "4") (pinfunction "4_4") (pintype "passive"))
      (node (ref "U$6") (pin "1B") (pinfunction "1B_1B") (pintype "output"))
    )
    (net (code "59") (name "Net-(JP10-Pad1)") (class "Default")
      (node (ref "JP10") (pin "1") (pinfunction "1_1") (pintype "bidirectional"))
      (node (ref "JP10") (pin "3") (pinfunction "3_3") (pintype "bidirectional"))
      (node (ref "JP10") (pin "5") (pinfunction "5_5") (pintype "bidirectional"))
      (node (ref "R7") (pin "2") (pinfunction "2_2") (pintype "passive"))
    )
    (net (code "60") (name "Net-(JP10-Pad2)") (class "Default")
      (node (ref "JP10") (pin "2") (pinfunction "2_2") (pintype "bidirectional"))
      (node (ref "U$6") (pin "MS3") (pinfunction "MS3_MS3") (pintype "input"))
    )
    (net (code "61") (name "Net-(JP10-Pad4)") (class "Default")
      (node (ref "JP10") (pin "4") (pinfunction "4_4") (pintype "bidirectional"))
      (node (ref "U$6") (pin "MS2") (pinfunction "MS2_MS2") (pintype "input"))
    )
    (net (code "62") (name "Net-(JP10-Pad6)") (class "Default")
      (node (ref "JP10") (pin "6") (pinfunction "6_6") (pintype "bidirectional"))
      (node (ref "U$6") (pin "MS1") (pinfunction "MS1_MS1") (pintype "input"))
    )
    (net (code "63") (name "Net-(Q1-PadG)") (class "Default")
      (node (ref "Q1") (pin "G") (pinfunction "G_G") (pintype "passive"))
      (node (ref "R14") (pin "2") (pinfunction "2_2") (pintype "passive"))
    )
    (net (code "64") (name "Net-(Q2-PadG)") (class "Default")
      (node (ref "Q2") (pin "G") (pinfunction "G_G") (pintype "passive"))
      (node (ref "R16") (pin "2") (pinfunction "2_2") (pintype "passive"))
    )
    (net (code "65") (name "Net-(Q3-PadG)") (class "Default")
      (node (ref "Q3") (pin "G") (pinfunction "G_G") (pintype "passive"))
      (node (ref "R18") (pin "2") (pinfunction "2_2") (pintype "passive"))
    )
    (net (code "66") (name "Net-(Q4-PadG)") (class "Default")
      (node (ref "Q4") (pin "G") (pinfunction "G_G") (pintype "passive"))
      (node (ref "R22") (pin "2") (pinfunction "2_2") (pintype "passive"))
    )
    (net (code "67") (name "Net-(T1-B)") (class "Default")
      (node (ref "R23") (pin "2") (pinfunction "2_2") (pintype "passive"))
      (node (ref "R24") (pin "2") (pinfunction "2_2") (pintype "passive"))
      (node (ref "T1") (pin "2") (pinfunction "B_2") (pintype "passive"))
    )
    (net (code "68") (name "Net-(T1-C)") (class "Default")
      (node (ref "JP17") (pin "2") (pinfunction "2_2") (pintype "passive"))
      (node (ref "T1") (pin "3") (pinfunction "C_3") (pintype "passive"))
    )
    (net (code "69") (name "Net-(T2-B)") (class "Default")
      (node (ref "R37") (pin "2") (pinfunction "2_2") (pintype "passive"))
      (node (ref "R42") (pin "2") (pinfunction "2_2") (pintype "passive"))
      (node (ref "T2") (pin "2") (pinfunction "B_2") (pintype "passive"))
    )
    (net (code "70") (name "Net-(T2-C)") (class "Default")
      (node (ref "JP16") (pin "2") (pinfunction "2_2") (pintype "passive"))
      (node (ref "T2") (pin "3") (pinfunction "C_3") (pintype "passive"))
    )
    (net (code "71") (name "Net-(U$2-SLEEP)") (class "Default")
      (node (ref "U$2") (pin "RST") (pinfunction "RST_RST") (pintype "input"))
      (node (ref "U$2") (pin "SLP") (pinfunction "SLEEP_SLP") (pintype "input"))
    )
    (net (code "72") (name "Net-(U$3-SLEEP)") (class "Default")
      (node (ref "U$3") (pin "RST") (pinfunction "RST_RST") (pintype "input"))
      (node (ref "U$3") (pin "SLP") (pinfunction "SLEEP_SLP") (pintype "input"))
    )
    (net (code "73") (name "Net-(U$4-SLEEP)") (class "Default")
      (node (ref "U$4") (pin "RST") (pinfunction "RST_RST") (pintype "input"))
      (node (ref "U$4") (pin "SLP") (pinfunction "SLEEP_SLP") (pintype "input"))
    )
    (net (code "74") (name "Net-(U$5-SLEEP)") (class "Default")
      (node (ref "U$5") (pin "RST") (pinfunction "RST_RST") (pintype "input"))
      (node (ref "U$5") (pin "SLP") (pinfunction "SLEEP_SLP") (pintype "input"))
    )
    (net (code "75") (name "Net-(U$6-SLEEP)") (class "Default")
      (node (ref "U$6") (pin "RST") (pinfunction "RST_RST") (pintype "input"))
      (node (ref "U$6") (pin "SLP") (pinfunction "SLEEP_SLP") (pintype "input"))
    )
    (net (code "76") (name "Net-(X3B-1)") (class "Default")
      (node (ref "Q1") (pin "D") (pinfunction "D_D") (pintype "passive"))
      (node (ref "X3") (pin "2") (pinfunction "1_2") (pintype "passive"))
    )
    (net (code "77") (name "Net-(X4B-1)") (class "Default")
      (node (ref "Q2") (pin "D") (pinfunction "D_D") (pintype "passive"))
      (node (ref "X4") (pin "2") (pinfunction "1_2") (pintype "passive"))
    )
    (net (code "78") (name "Net-(X5B-1)") (class "Default")
      (node (ref "Q3") (pin "D") (pinfunction "D_D") (pintype "passive"))
      (node (ref "X5") (pin "2") (pinfunction "1_2") (pintype "passive"))
    )
    (net (code "79") (name "Net-(X6B-1)") (class "Default")
      (node (ref "Q4") (pin "D") (pinfunction "D_D") (pintype "passive"))
      (node (ref "X6") (pin "2") (pinfunction "1_2") (pintype "passive"))
    )
    (net (code "80") (name "P1_22-3RD-SMALL-FET") (class "Default")
      (node (ref "R23") (pin "1") (pinfunction "1_1") (pintype "passive"))
      (node (ref "U$1") (pin "P1_22-3RD-SMALL-FET") (pinfunction "P1_22-3RD-SMALL-FET_P1_22-3RD-SMALL-FET") (pintype "bidirectional"))
    )
    (net (code "81") (name "P1_23-3RD-LARGE-FET") (class "Default")
      (node (ref "R37") (pin "1") (pinfunction "1_1") (pintype "passive"))
      (node (ref "U$1") (pin "P1_23-3RD-LARGE-FET") (pinfunction "P1_23-3RD-LARGE-FET_P1_23-3RD-LARGE-FET") (pintype "bidirectional"))
    )
    (net (code "82") (name "P1_30_CLICK-ON-RRD") (class "Default")
      (node (ref "EXP1") (pin "2") (pinfunction "KL_2") (pintype "passive"))
      (node (ref "U$1") (pin "P1_30_CLICK-ON-RRD") (pinfunction "P1_30_CLICK-ON-RRD_P1_30_CLICK-ON-RRD") (pintype "bidirectional"))
    )
    (net (code "83") (name "P2.6_FAN_FET") (class "Default")
      (node (ref "R15") (pin "1") (pinfunction "1_1") (pintype "passive"))
      (node (ref "R16") (pin "1") (pinfunction "1_1") (pintype "passive"))
      (node (ref "U$1") (pin "P2.6_FAN_FET") (pinfunction "P2.6_FAN_FET_P2.6_FAN_FET") (pintype "bidirectional"))
    )
    (net (code "84") (name "P2.7_HOTEND_FET") (class "Default")
      (node (ref "R13") (pin "1") (pinfunction "1_1") (pintype "passive"))
      (node (ref "R14") (pin "1") (pinfunction "1_1") (pintype "passive"))
      (node (ref "U$1") (pin "P2.7_HOTEND_FET") (pinfunction "P2.7_HOTEND_FET_P2.7_HOTEND_FET") (pintype "bidirectional"))
    )
    (net (code "85") (name "PSUON") (class "Default")
      (node (ref "JP11") (pin "2") (pinfunction "2_2") (pintype "passive"))
      (node (ref "X1") (pin "16") (pinfunction "S_16") (pintype "passive"))
    )
    (net (code "86") (name "PWM0_PSU_OUT") (class "Default")
      (node (ref "R21") (pin "1") (pinfunction "1_1") (pintype "passive"))
      (node (ref "R22") (pin "1") (pinfunction "1_1") (pintype "passive"))
      (node (ref "U$1") (pin "PWM0_PSU_OUT") (pinfunction "PWM0_PSU_OUT_PWM0_PSU_OUT") (pintype "bidirectional"))
    )
    (net (code "87") (name "PWM1_BED_HEATER") (class "Default")
      (node (ref "R17") (pin "1") (pinfunction "1_1") (pintype "passive"))
      (node (ref "R18") (pin "1") (pinfunction "1_1") (pintype "passive"))
      (node (ref "U$1") (pin "PWM1_BED_HEATER") (pinfunction "PWM1_BED_HEATER_PWM1_BED_HEATER") (pintype "bidirectional"))
    )
    (net (code "88") (name "RX_0") (class "Default")
      (node (ref "JP18") (pin "2") (pinfunction "2_2") (pintype "passive"))
      (node (ref "U$1") (pin "RX_0") (pinfunction "RX_0_RX_0") (pintype "bidirectional"))
    )
    (net (code "89") (name "SCK1") (class "Default")
      (node (ref "EXP1") (pin "5") (pinfunction "KL_5") (pintype "passive"))
      (node (ref "U$1") (pin "SCK1") (pinfunction "SCK1_SCK1") (pintype "bidirectional"))
    )
    (net (code "90") (name "SD-CD-ON-RRD") (class "Default")
      (node (ref "EXP2") (pin "7") (pinfunction "KL_7") (pintype "passive"))
    )
    (net (code "91") (name "SD-CS-ON-RRD") (class "Default")
      (node (ref "EXP2") (pin "4") (pinfunction "KL_4") (pintype "passive"))
    )
    (net (code "92") (name "SD_CD{slash}KILL-ON-RRD") (class "Default")
      (node (ref "EXP2") (pin "8") (pinfunction "KL_8") (pintype "passive"))
    )
    (net (code "93") (name "SD_IRQ-ENC-A-ON-RRD") (class "Default")
      (node (ref "EXP2") (pin "5") (pinfunction "KL_5") (pintype "passive"))
      (node (ref "U$1") (pin "SD_IRQ-ENC-A-ON-RRD") (pinfunction "SD_IRQ-ENC-A-ON-RRD_SD_IRQ-ENC-A-ON-RRD") (pintype "bidirectional"))
    )
    (net (code "94") (name "SD_MISO") (class "Default")
      (node (ref "EXP2") (pin "1") (pinfunction "KL_1") (pintype "passive"))
    )
    (net (code "95") (name "SD_MOSI") (class "Default")
      (node (ref "EXP2") (pin "6") (pinfunction "KL_6") (pintype "passive"))
    )
    (net (code "96") (name "SD_SCK") (class "Default")
      (node (ref "EXP2") (pin "2") (pinfunction "KL_2") (pintype "passive"))
    )
    (net (code "97") (name "SD_WP-ENC-B-ON-RRD") (class "Default")
      (node (ref "EXP2") (pin "3") (pinfunction "KL_3") (pintype "passive"))
      (node (ref "U$1") (pin "SD_WP-ENC-B-ON-RRD") (pinfunction "SD_WP-ENC-B-ON-RRD_SD_WP-ENC-B-ON-RRD") (pintype "bidirectional"))
    )
    (net (code "98") (name "SSEL1") (class "Default")
      (node (ref "EXP1") (pin "4") (pinfunction "KL_4") (pintype "passive"))
      (node (ref "U$1") (pin "SSEL1") (pinfunction "SSEL1_SSEL1") (pintype "bidirectional"))
    )
    (net (code "99") (name "STP1") (class "Default")
      (node (ref "U$1") (pin "STP1") (pinfunction "STP1_STP1") (pintype "bidirectional"))
      (node (ref "U$2") (pin "STEP") (pinfunction "STEP_STEP") (pintype "input"))
    )
    (net (code "100") (name "STP2") (class "Default")
      (node (ref "U$1") (pin "STP2") (pinfunction "STP2_STP2") (pintype "bidirectional"))
      (node (ref "U$3") (pin "STEP") (pinfunction "STEP_STEP") (pintype "input"))
    )
    (net (code "101") (name "STP3") (class "Default")
      (node (ref "U$1") (pin "STP3") (pinfunction "STP3_STP3") (pintype "bidirectional"))
      (node (ref "U$4") (pin "STEP") (pinfunction "STEP_STEP") (pintype "input"))
    )
    (net (code "102") (name "STP4") (class "Default")
      (node (ref "U$1") (pin "STP4") (pinfunction "STP4_STP4") (pintype "bidirectional"))
      (node (ref "U$5") (pin "STEP") (pinfunction "STEP_STEP") (pintype "input"))
    )
    (net (code "103") (name "STP5") (class "Default")
      (node (ref "U$1") (pin "STP5") (pinfunction "STP5_STP5") (pintype "bidirectional"))
      (node (ref "U$6") (pin "STEP") (pinfunction "STEP_STEP") (pintype "input"))
    )
    (net (code "104") (name "TH1_HOTEND") (class "Default")
      (node (ref "C45") (pin "1") (pinfunction "1_1") (pintype "passive"))
      (node (ref "JP13") (pin "2") (pinfunction "2_2") (pintype "passive"))
      (node (ref "R10") (pin "1") (pinfunction "1_1") (pintype "passive"))
      (node (ref "U$1") (pin "TH1_HOTEND") (pinfunction "TH1_HOTEND_TH1_HOTEND") (pintype "bidirectional"))
    )
    (net (code "105") (name "TH2_BED") (class "Default")
      (node (ref "C44") (pin "1") (pinfunction "1_1") (pintype "passive"))
      (node (ref "JP12") (pin "2") (pinfunction "2_2") (pintype "passive"))
      (node (ref "R9") (pin "1") (pinfunction "1_1") (pintype "passive"))
      (node (ref "U$1") (pin "TH2_BED") (pinfunction "TH2_BED_TH2_BED") (pintype "bidirectional"))
    )
    (net (code "106") (name "TH3") (class "Default")
      (node (ref "C46") (pin "1") (pinfunction "1_1") (pintype "passive"))
      (node (ref "JP14") (pin "2") (pinfunction "2_2") (pintype "passive"))
      (node (ref "R11") (pin "1") (pinfunction "1_1") (pintype "passive"))
      (node (ref "U$1") (pin "TH3") (pinfunction "TH3_TH3") (pintype "bidirectional"))
    )
    (net (code "107") (name "TH4") (class "Default")
      (node (ref "C47") (pin "1") (pinfunction "1_1") (pintype "passive"))
      (node (ref "JP15") (pin "2") (pinfunction "2_2") (pintype "passive"))
      (node (ref "R12") (pin "1") (pinfunction "1_1") (pintype "passive"))
      (node (ref "U$1") (pin "TH4") (pinfunction "TH4_TH4") (pintype "bidirectional"))
    )
    (net (code "108") (name "TX_0") (class "Default")
      (node (ref "JP18") (pin "1") (pinfunction "1_1") (pintype "passive"))
      (node (ref "U$1") (pin "TX_0") (pinfunction "TX_0_TX_0") (pintype "bidirectional"))
    )
    (net (code "109") (name "X_MAX") (class "Default")
      (node (ref "U$1") (pin "X_MAX") (pinfunction "X_MAX_X_MAX") (pintype "bidirectional"))
      (node (ref "XMX") (pin "3") (pinfunction "3_3") (pintype "passive"))
    )
    (net (code "110") (name "X_MIN") (class "Default")
      (node (ref "U$1") (pin "X_MIN") (pinfunction "X_MIN_X_MIN") (pintype "bidirectional"))
      (node (ref "XMN") (pin "3") (pinfunction "3_3") (pintype "passive"))
    )
    (net (code "111") (name "Y_MAX") (class "Default")
      (node (ref "U$1") (pin "Y_MAX") (pinfunction "Y_MAX_Y_MAX") (pintype "bidirectional"))
      (node (ref "YMX") (pin "3") (pinfunction "3_3") (pintype "passive"))
    )
    (net (code "112") (name "Y_MIN") (class "Default")
      (node (ref "U$1") (pin "Y_MIN") (pinfunction "Y_MIN_Y_MIN") (pintype "bidirectional"))
      (node (ref "YMN") (pin "3") (pinfunction "3_3") (pintype "passive"))
    )
    (net (code "113") (name "Z_MAX") (class "Default")
      (node (ref "U$1") (pin "Z_MAX") (pinfunction "Z_MAX_Z_MAX") (pintype "bidirectional"))
      (node (ref "ZMX") (pin "3") (pinfunction "3_3") (pintype "passive"))
    )
    (net (code "114") (name "Z_MIN") (class "Default")
      (node (ref "U$1") (pin "Z_MIN") (pinfunction "Z_MIN_Z_MIN") (pintype "bidirectional"))
      (node (ref "ZMN") (pin "3") (pinfunction "3_3") (pintype "passive"))
    )
    (net (code "115") (name "unconnected-(EXP1G-KL-Pad6)") (class "Default")
      (node (ref "EXP1") (pin "6") (pinfunction "KL_6") (pintype "passive"))
    )
    (net (code "116") (name "unconnected-(EXP1H-KL-Pad7)") (class "Default")
      (node (ref "EXP1") (pin "7") (pinfunction "KL_7") (pintype "passive"))
    )
    (net (code "117") (name "unconnected-(EXP1I-KL-Pad8)") (class "Default")
      (node (ref "EXP1") (pin "8") (pinfunction "KL_8") (pintype "passive"))
    )
    (net (code "118") (name "unconnected-(EXP2B-KL-Pad10)") (class "Default")
      (node (ref "EXP2") (pin "10") (pinfunction "KL_10") (pintype "passive"))
    )
    (net (code "119") (name "unconnected-(X1A-S-Pad1)") (class "Default")
      (node (ref "X1") (pin "1") (pinfunction "S_1") (pintype "passive"))
    )
    (net (code "120") (name "unconnected-(X1D-S-Pad12)") (class "Default")
      (node (ref "X1") (pin "12") (pinfunction "S_12") (pintype "passive"))
    )
    (net (code "121") (name "unconnected-(X1E-S-Pad13)") (class "Default")
      (node (ref "X1") (pin "13") (pinfunction "S_13") (pintype "passive"))
    )
    (net (code "122") (name "unconnected-(X1F-S-Pad14)") (class "Default")
      (node (ref "X1") (pin "14") (pinfunction "S_14") (pintype "passive"))
    )
    (net (code "123") (name "unconnected-(X1G-S-Pad15)") (class "Default")
      (node (ref "X1") (pin "15") (pinfunction "S_15") (pintype "passive"))
    )
    (net (code "124") (name "unconnected-(X1L-S-Pad2)") (class "Default")
      (node (ref "X1") (pin "2") (pinfunction "S_2") (pintype "passive"))
    )
    (net (code "125") (name "unconnected-(X1M-S-Pad20)") (class "Default")
      (node (ref "X1") (pin "20") (pinfunction "S_20") (pintype "passive"))
    )
    (net (code "126") (name "unconnected-(X1O-S-Pad22)") (class "Default")
      (node (ref "X1") (pin "22") (pinfunction "S_22") (pintype "passive"))
    )
    (net (code "127") (name "unconnected-(X1P-S-Pad23)") (class "Default")
      (node (ref "X1") (pin "23") (pinfunction "S_23") (pintype "passive"))
    )
    (net (code "128") (name "unconnected-(X1Q-S-Pad24)") (class "Default")
      (node (ref "X1") (pin "24") (pinfunction "S_24") (pintype "passive"))
    )
    (net (code "129") (name "unconnected-(X1R-S-Pad3)") (class "Default")
      (node (ref "X1") (pin "3") (pinfunction "S_3") (pintype "passive"))
    )
    (net (code "130") (name "unconnected-(X1S-S-Pad4)") (class "Default")
      (node (ref "X1") (pin "4") (pinfunction "S_4") (pintype "passive"))
    )
    (net (code "131") (name "unconnected-(X1T-S-Pad5)") (class "Default")
      (node (ref "X1") (pin "5") (pinfunction "S_5") (pintype "passive"))
    )
    (net (code "132") (name "unconnected-(X1U-S-Pad6)") (class "Default")
      (node (ref "X1") (pin "6") (pinfunction "S_6") (pintype "passive"))
    )
    (net (code "133") (name "unconnected-(X1V-S-Pad7)") (class "Default")
      (node (ref "X1") (pin "7") (pinfunction "S_7") (pintype "passive"))
    )
    (net (code "134") (name "unconnected-(X1W-S-Pad8)") (class "Default")
      (node (ref "X1") (pin "8") (pinfunction "S_8") (pintype "passive"))
    )
  )
)
